# main_backup.net
KiCad netlist of a schematic drawn in Altium Designer
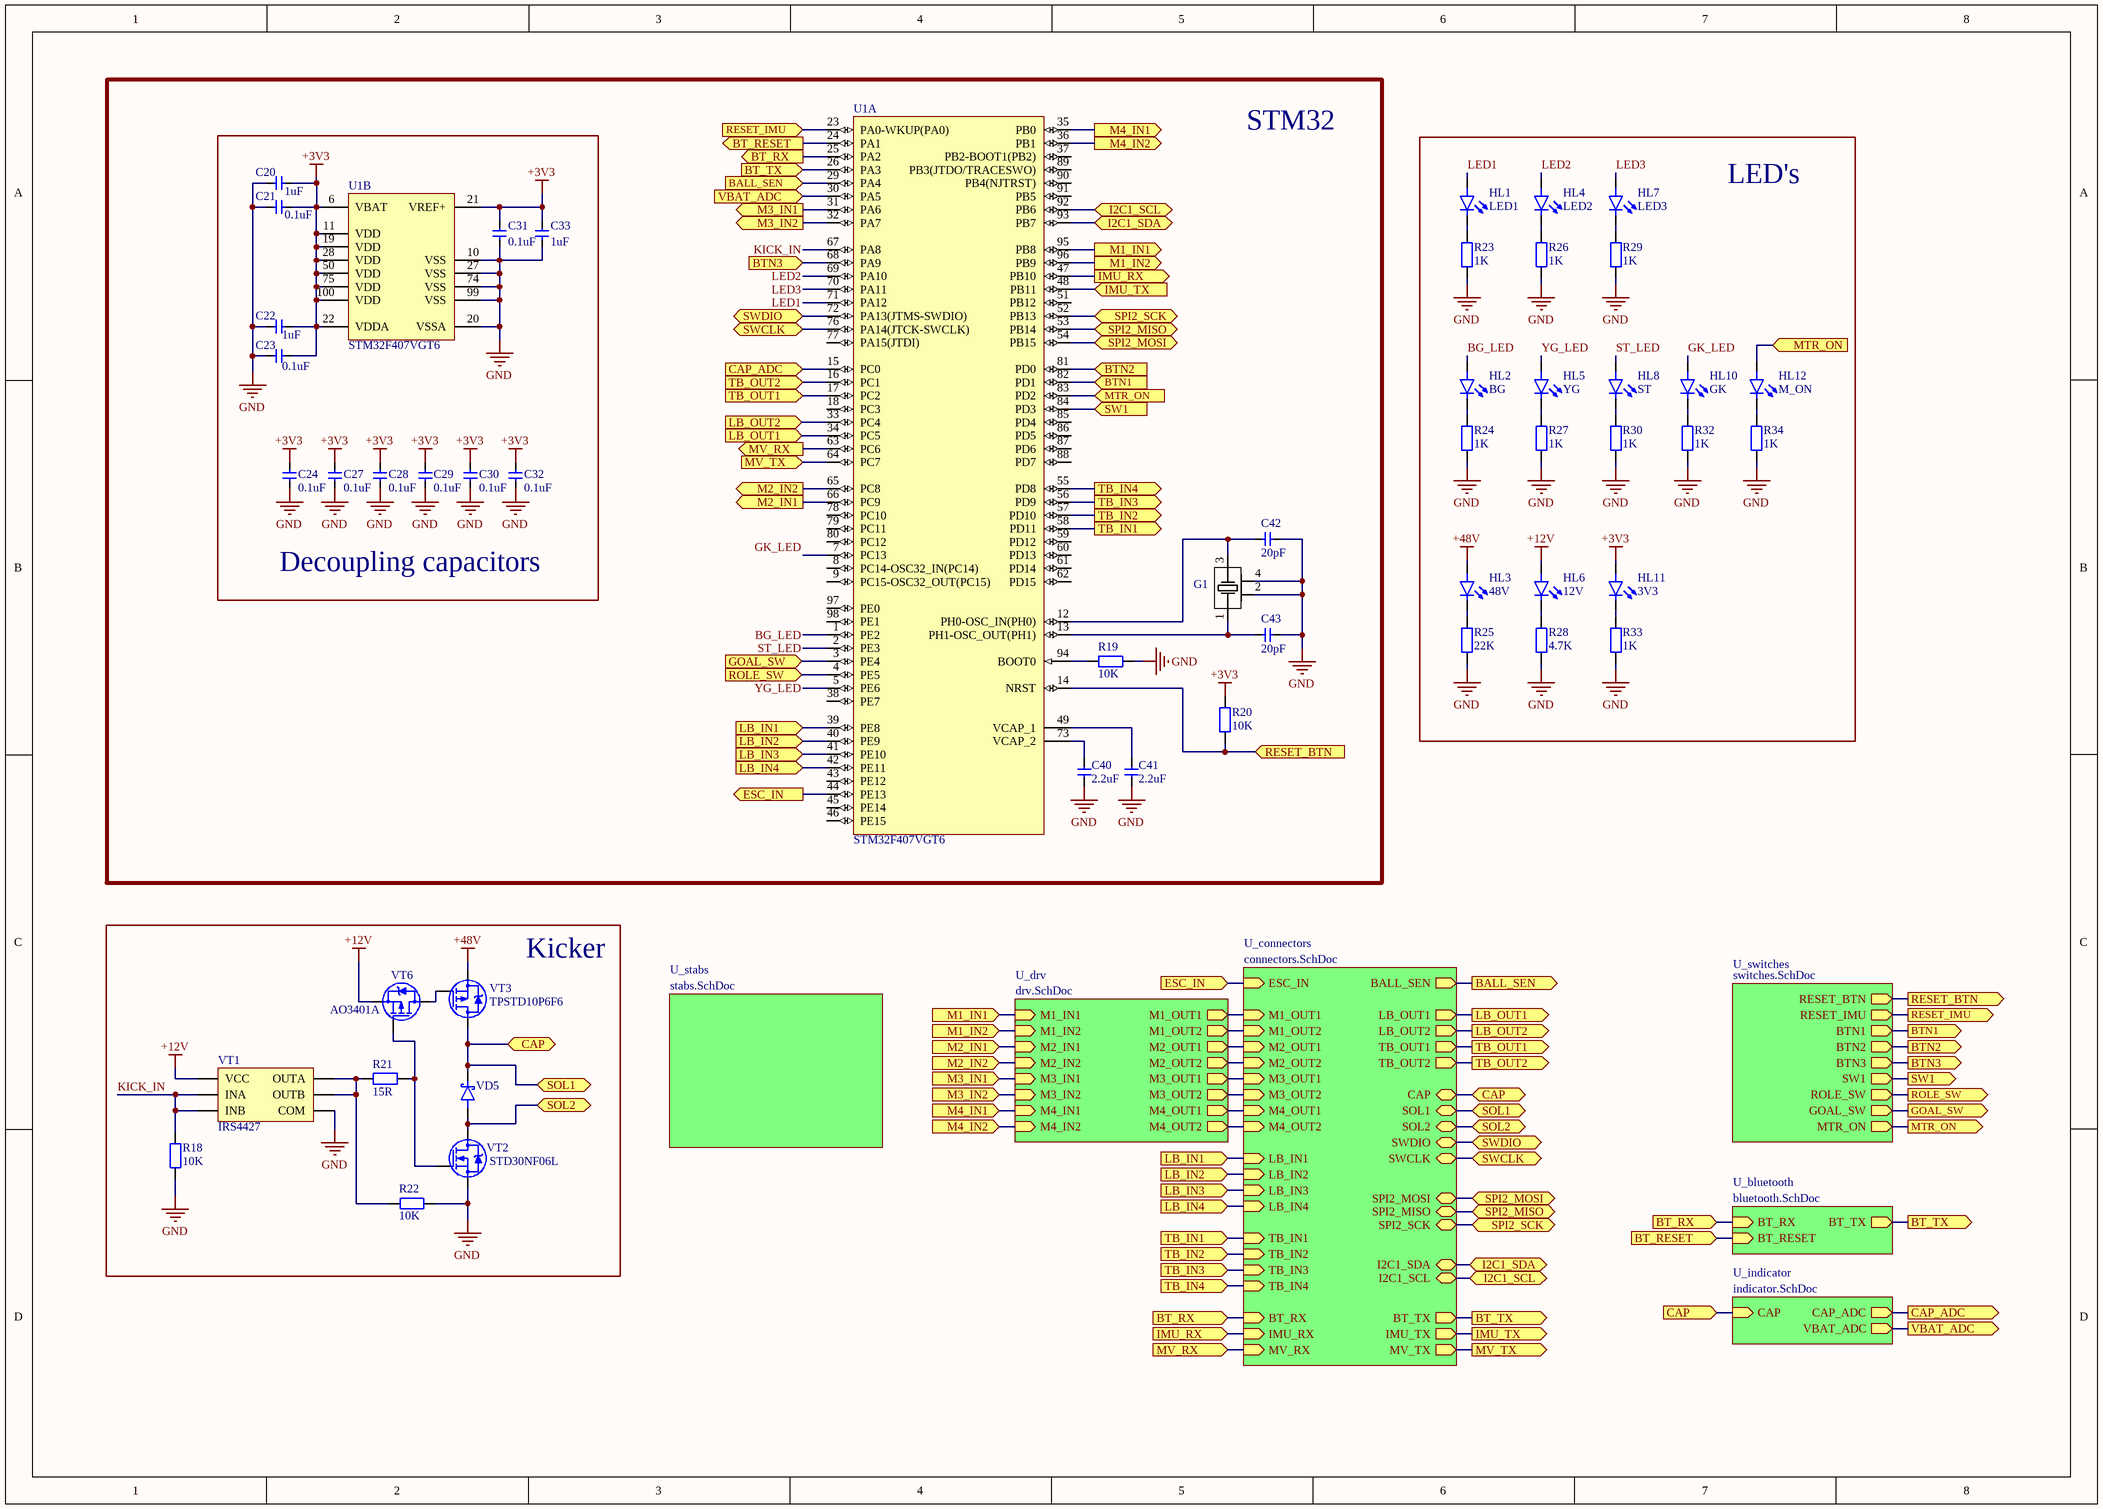
[diagram p0: main_backup.SchDoc]

(export (version "E")
  (design (tool "Eeschema 10.0.6"))
  (components
    (comp (ref "C20")
      (value "1uF")
      (footprint "CAP0805")
      (description "Ceramic SMD Cap")
      (libsource (lib "Asterisk") (part "CAP Ceramic"))
    )
    (comp (ref "C21")
      (value "0.1uF")
      (footprint "CAP0805")
      (description "Ceramic SMD Cap")
      (libsource (lib "Asterisk") (part "CAP Ceramic"))
    )
    (comp (ref "C22")
      (value "1uF")
      (footprint "CAP0805")
      (description "Ceramic SMD Cap")
      (libsource (lib "Asterisk") (part "CAP Ceramic"))
    )
    (comp (ref "C23")
      (value "0.1uF")
      (footprint "CAP0805")
      (description "Ceramic SMD Cap")
      (libsource (lib "Asterisk") (part "CAP Ceramic"))
    )
    (comp (ref "C24")
      (value "0.1uF")
      (footprint "CAP0805")
      (description "Ceramic SMD Cap")
      (libsource (lib "Asterisk") (part "CAP Ceramic"))
    )
    (comp (ref "C27")
      (value "0.1uF")
      (footprint "CAP0805")
      (description "Ceramic SMD Cap")
      (libsource (lib "Asterisk") (part "CAP Ceramic"))
    )
    (comp (ref "C28")
      (value "0.1uF")
      (footprint "CAP0805")
      (description "Ceramic SMD Cap")
      (libsource (lib "Asterisk") (part "CAP Ceramic"))
    )
    (comp (ref "C29")
      (value "0.1uF")
      (footprint "CAP0805")
      (description "Ceramic SMD Cap")
      (libsource (lib "Asterisk") (part "CAP Ceramic"))
    )
    (comp (ref "C30")
      (value "0.1uF")
      (footprint "CAP0805")
      (description "Ceramic SMD Cap")
      (libsource (lib "Asterisk") (part "CAP Ceramic"))
    )
    (comp (ref "C31")
      (value "0.1uF")
      (footprint "CAP0805")
      (description "Ceramic SMD Cap")
      (libsource (lib "Asterisk") (part "CAP Ceramic"))
    )
    (comp (ref "C32")
      (value "0.1uF")
      (footprint "CAP0805")
      (description "Ceramic SMD Cap")
      (libsource (lib "Asterisk") (part "CAP Ceramic"))
    )
    (comp (ref "C33")
      (value "1uF")
      (footprint "CAP0805")
      (description "Ceramic SMD Cap")
      (libsource (lib "Asterisk") (part "CAP Ceramic"))
    )
    (comp (ref "C40")
      (value "2.2uF")
      (footprint "CAP0805")
      (description "Ceramic SMD Cap")
      (libsource (lib "") (part "CAP Ceramic_1"))
    )
    (comp (ref "C41")
      (value "2.2uF")
      (footprint "CAP0805")
      (description "Ceramic SMD Cap")
      (libsource (lib "") (part "CAP Ceramic_1"))
    )
    (comp (ref "C42")
      (value "20pF")
      (footprint "CAP0805")
      (description "Ceramic SMD Cap")
      (libsource (lib "Asterisk") (part "CAP Ceramic"))
    )
    (comp (ref "C43")
      (value "20pF")
      (footprint "CAP0805")
      (description "Ceramic SMD Cap")
      (libsource (lib "Asterisk") (part "CAP Ceramic"))
    )
    (comp (ref "G1")
      (value "8 MHz")
      (footprint "TSX-3225")
      (description "24MHz ±10ppm Crystal 9pF 40 Ohms 4-SMD, No Lead")
      (fields
        (field (name "PART NUMBER") "TSX-3225 24.0000MF15X-AC6")
        (field (name "DIGI-KEY PART NUMBER") "SER4180CT-ND")
      )
      (libsource (lib "SssAccesDatbase") (part "CTX957CT"))
    )
    (comp (ref "HL1")
      (value "LED1")
      (footprint "LED0603_WHITE")
      (description "LED smd")
      (libsource (lib "Asterisk") (part "LED"))
    )
    (comp (ref "HL2")
      (value "BG")
      (footprint "LED0603_WHITE")
      (description "LED smd")
      (libsource (lib "Asterisk") (part "LED"))
    )
    (comp (ref "HL3")
      (value "48V")
      (footprint "LED0603_GREEN")
      (description "LED smd")
      (libsource (lib "Asterisk") (part "LED"))
    )
    (comp (ref "HL4")
      (value "LED2")
      (footprint "LED0603_WHITE")
      (description "LED smd")
      (libsource (lib "Asterisk") (part "LED"))
    )
    (comp (ref "HL5")
      (value "YG")
      (footprint "LED0603_WHITE")
      (description "LED smd")
      (libsource (lib "Asterisk") (part "LED"))
    )
    (comp (ref "HL6")
      (value "12V")
      (footprint "LED0603_GREEN")
      (description "LED smd")
      (libsource (lib "Asterisk") (part "LED"))
    )
    (comp (ref "HL7")
      (value "LED3")
      (footprint "LED0603_WHITE")
      (description "LED smd")
      (libsource (lib "Asterisk") (part "LED"))
    )
    (comp (ref "HL8")
      (value "ST")
      (footprint "LED0603_WHITE")
      (description "LED smd")
      (libsource (lib "Asterisk") (part "LED"))
    )
    (comp (ref "HL10")
      (value "GK")
      (footprint "LED0603_WHITE")
      (description "LED smd")
      (libsource (lib "Asterisk") (part "LED"))
    )
    (comp (ref "HL11")
      (value "3V3")
      (footprint "LED0603_GREEN")
      (description "LED smd")
      (libsource (lib "Asterisk") (part "LED"))
    )
    (comp (ref "HL12")
      (value "M_ON")
      (footprint "LED0603_RED")
      (description "LED smd")
      (libsource (lib "Asterisk") (part "LED"))
    )
    (comp (ref "R18")
      (value "10K")
      (footprint "RES0805")
      (description "RES smd")
      (libsource (lib "Asterisk") (part "RES"))
    )
    (comp (ref "R19")
      (value "10K")
      (footprint "RES0805")
      (description "RES smd")
      (libsource (lib "Asterisk") (part "RES"))
    )
    (comp (ref "R20")
      (value "10K")
      (footprint "RES0805")
      (description "RES smd")
      (libsource (lib "Asterisk") (part "RES"))
    )
    (comp (ref "R21")
      (value "15R")
      (footprint "RES1206")
      (description "RES smd")
      (libsource (lib "Asterisk") (part "RES"))
    )
    (comp (ref "R22")
      (value "10K")
      (footprint "RES0805")
      (description "RES smd")
      (libsource (lib "Asterisk") (part "RES"))
    )
    (comp (ref "R23")
      (value "1K")
      (footprint "RES0805")
      (description "RES smd")
      (libsource (lib "Asterisk") (part "RES"))
    )
    (comp (ref "R24")
      (value "1K")
      (footprint "RES0805")
      (description "RES smd")
      (libsource (lib "Asterisk") (part "RES"))
    )
    (comp (ref "R25")
      (value "22K")
      (footprint "RES0805")
      (description "RES smd")
      (libsource (lib "Asterisk") (part "RES"))
    )
    (comp (ref "R26")
      (value "1K")
      (footprint "RES0805")
      (description "RES smd")
      (libsource (lib "Asterisk") (part "RES"))
    )
    (comp (ref "R27")
      (value "1K")
      (footprint "RES0805")
      (description "RES smd")
      (libsource (lib "Asterisk") (part "RES"))
    )
    (comp (ref "R28")
      (value "4.7K")
      (footprint "RES0805")
      (description "RES smd")
      (libsource (lib "Asterisk") (part "RES"))
    )
    (comp (ref "R29")
      (value "1K")
      (footprint "RES0805")
      (description "RES smd")
      (libsource (lib "Asterisk") (part "RES"))
    )
    (comp (ref "R30")
      (value "1K")
      (footprint "RES0805")
      (description "RES smd")
      (libsource (lib "Asterisk") (part "RES"))
    )
    (comp (ref "R32")
      (value "1K")
      (footprint "RES0805")
      (description "RES smd")
      (libsource (lib "Asterisk") (part "RES"))
    )
    (comp (ref "R33")
      (value "1K")
      (footprint "RES0805")
      (description "RES smd")
      (libsource (lib "Asterisk") (part "RES"))
    )
    (comp (ref "R34")
      (value "1K")
      (footprint "RES0805")
      (description "RES smd")
      (libsource (lib "Asterisk") (part "RES"))
    )
    (comp (ref "U1")
      (value "STM32F407VGT6")
      (footprint "LQFP100")
      (fields (field (name "MANUFACTURER") "STMicroelectronics"))
      (libsource (lib "Asterisk") (part "STM32F407VGT6"))
    )
    (comp (ref "VD5")
      (value "Diode Schottky")
      (footprint "DO-214AC (SMA)")
      (libsource (lib "Asterisk") (part "Diode Schottky"))
    )
    (comp (ref "VT1")
      (value "IRS4427")
      (footprint "SOIC-8")
      (description "Mosfet driver")
      (libsource (lib "Asterisk") (part "IRS4427"))
    )
    (comp (ref "VT2")
      (value "STD30NF06L")
      (footprint "DPAK")
      (description "N-MOSFET\r\nUds = 60 V\r\nIds = 30 A\r\nRds = 0.023 Ohm\r\nP = 55 W")
      (libsource (lib "Asterisk") (part "STD30NF06L"))
    )
    (comp (ref "VT3")
      (value "TPSTD10P6F6")
      (footprint "DPAK")
      (description "P-MOSFET\r\nUds = 60 V\r\nIds = 13 A\r\nRds = 0.100 Ohm\r\nP = 60 W")
      (libsource (lib "Asterisk") (part "TPSTD10P6F6"))
    )
    (comp (ref "VT6")
      (value "AO3401A")
      (footprint "SOT-23-3")
      (description "P-MOSFET\r\nUds = 30 V\r\nIds = 4.2 A\r\nRds = 0.050 Ohm\r\nP = 1.4 W")
      (libsource (lib "Asterisk") (part "AO3401A"))
    )
  )
  (nets
    (net (code "1") (name "+3V3") (class "Default")
      (node (ref "C20") (pin "1") (pinfunction "1_1") (pintype "passive"))
      (node (ref "C21") (pin "1") (pinfunction "1_1") (pintype "passive"))
      (node (ref "C22") (pin "1") (pinfunction "1_1") (pintype "passive"))
      (node (ref "C23") (pin "1") (pinfunction "1_1") (pintype "passive"))
      (node (ref "C24") (pin "1") (pinfunction "1_1") (pintype "passive"))
      (node (ref "C27") (pin "1") (pinfunction "1_1") (pintype "passive"))
      (node (ref "C28") (pin "1") (pinfunction "1_1") (pintype "passive"))
      (node (ref "C29") (pin "1") (pinfunction "1_1") (pintype "passive"))
      (node (ref "C30") (pin "1") (pinfunction "1_1") (pintype "passive"))
      (node (ref "C31") (pin "2") (pinfunction "2_2") (pintype "passive"))
      (node (ref "C32") (pin "1") (pinfunction "1_1") (pintype "passive"))
      (node (ref "C33") (pin "2") (pinfunction "2_2") (pintype "passive"))
      (node (ref "HL11") (pin "2") (pinfunction "A_2") (pintype "passive"))
      (node (ref "R20") (pin "1") (pinfunction "1_1") (pintype "passive"))
      (node (ref "U1") (pin "100") (pinfunction "VDD_100") (pintype "power_in"))
      (node (ref "U1") (pin "11") (pinfunction "VDD_11") (pintype "power_in"))
      (node (ref "U1") (pin "19") (pinfunction "VDD_19") (pintype "power_in"))
      (node (ref "U1") (pin "21") (pinfunction "VREF+_21") (pintype "power_in"))
      (node (ref "U1") (pin "22") (pinfunction "VDDA_22") (pintype "power_in"))
      (node (ref "U1") (pin "28") (pinfunction "VDD_28") (pintype "power_in"))
      (node (ref "U1") (pin "50") (pinfunction "VDD_50") (pintype "power_in"))
      (node (ref "U1") (pin "6") (pinfunction "VBAT_6") (pintype "power_in"))
      (node (ref "U1") (pin "75") (pinfunction "VDD_75") (pintype "power_in"))
    )
    (net (code "2") (name "+12V") (class "Default")
      (node (ref "HL6") (pin "2") (pinfunction "A_2") (pintype "passive"))
      (node (ref "VT1") (pin "6") (pinfunction "VCC_6") (pintype "passive"))
      (node (ref "VT6") (pin "S") (pinfunction "S_S") (pintype "passive"))
    )
    (net (code "3") (name "+48V") (class "Default")
      (node (ref "HL3") (pin "2") (pinfunction "A_2") (pintype "passive"))
      (node (ref "VT3") (pin "S") (pinfunction "S_S") (pintype "passive"))
    )
    (net (code "4") (name "/BALL_SEN") (class "Default")
      (node (ref "U1") (pin "29") (pinfunction "PA4_29") (pintype "bidirectional"))
    )
    (net (code "5") (name "/BG_LED") (class "Default")
      (node (ref "HL2") (pin "2") (pinfunction "A_2") (pintype "passive"))
      (node (ref "U1") (pin "1") (pinfunction "PE2_1") (pintype "bidirectional"))
    )
    (net (code "6") (name "/BTN1") (class "Default")
      (node (ref "U1") (pin "82") (pinfunction "PD1_82") (pintype "bidirectional"))
    )
    (net (code "7") (name "/BTN2") (class "Default")
      (node (ref "U1") (pin "81") (pinfunction "PD0_81") (pintype "bidirectional"))
    )
    (net (code "8") (name "/BTN3") (class "Default")
      (node (ref "U1") (pin "68") (pinfunction "PA9_68") (pintype "bidirectional"))
    )
    (net (code "9") (name "/BT_RESET") (class "Default")
      (node (ref "U1") (pin "24") (pinfunction "PA1_24") (pintype "bidirectional"))
    )
    (net (code "10") (name "/BT_RX") (class "Default")
      (node (ref "U1") (pin "25") (pinfunction "PA2_25") (pintype "bidirectional"))
    )
    (net (code "11") (name "/BT_TX") (class "Default")
      (node (ref "U1") (pin "26") (pinfunction "PA3_26") (pintype "bidirectional"))
    )
    (net (code "12") (name "/CAP") (class "Default")
      (node (ref "VD5") (pin "K") (pinfunction "K_K") (pintype "passive"))
      (node (ref "VT3") (pin "D") (pinfunction "D_D") (pintype "passive"))
    )
    (net (code "13") (name "/CAP_ADC") (class "Default")
      (node (ref "U1") (pin "15") (pinfunction "PC0_15") (pintype "bidirectional"))
    )
    (net (code "14") (name "/ESC_IN") (class "Default")
      (node (ref "U1") (pin "44") (pinfunction "PE13_44") (pintype "bidirectional"))
    )
    (net (code "15") (name "/GK_LED") (class "Default")
      (node (ref "HL10") (pin "2") (pinfunction "A_2") (pintype "passive"))
      (node (ref "U1") (pin "7") (pinfunction "PC13_7") (pintype "bidirectional"))
    )
    (net (code "16") (name "/GOAL_SW") (class "Default")
      (node (ref "U1") (pin "3") (pinfunction "PE4_3") (pintype "bidirectional"))
    )
    (net (code "17") (name "/I2C1_SCL") (class "Default")
      (node (ref "U1") (pin "92") (pinfunction "PB6_92") (pintype "bidirectional"))
    )
    (net (code "18") (name "/I2C1_SDA") (class "Default")
      (node (ref "U1") (pin "93") (pinfunction "PB7_93") (pintype "bidirectional"))
    )
    (net (code "19") (name "/IMU_RX") (class "Default")
      (node (ref "U1") (pin "47") (pinfunction "PB10_47") (pintype "bidirectional"))
    )
    (net (code "20") (name "/IMU_TX") (class "Default")
      (node (ref "U1") (pin "48") (pinfunction "PB11_48") (pintype "bidirectional"))
    )
    (net (code "21") (name "/KICK_IN") (class "Default")
      (node (ref "R18") (pin "2") (pinfunction "2_2") (pintype "passive"))
      (node (ref "U1") (pin "67") (pinfunction "PA8_67") (pintype "bidirectional"))
      (node (ref "VT1") (pin "2") (pinfunction "INA_2") (pintype "passive"))
      (node (ref "VT1") (pin "4") (pinfunction "INB_4") (pintype "passive"))
    )
    (net (code "22") (name "/LB_IN1") (class "Default")
      (node (ref "U1") (pin "39") (pinfunction "PE8_39") (pintype "bidirectional"))
    )
    (net (code "23") (name "/LB_IN2") (class "Default")
      (node (ref "U1") (pin "40") (pinfunction "PE9_40") (pintype "bidirectional"))
    )
    (net (code "24") (name "/LB_IN3") (class "Default")
      (node (ref "U1") (pin "41") (pinfunction "PE10_41") (pintype "bidirectional"))
    )
    (net (code "25") (name "/LB_IN4") (class "Default")
      (node (ref "U1") (pin "42") (pinfunction "PE11_42") (pintype "bidirectional"))
    )
    (net (code "26") (name "/LB_OUT1") (class "Default")
      (node (ref "U1") (pin "34") (pinfunction "PC5_34") (pintype "bidirectional"))
    )
    (net (code "27") (name "/LB_OUT2") (class "Default")
      (node (ref "U1") (pin "33") (pinfunction "PC4_33") (pintype "bidirectional"))
    )
    (net (code "28") (name "/LED1") (class "Default")
      (node (ref "HL1") (pin "2") (pinfunction "A_2") (pintype "passive"))
      (node (ref "U1") (pin "71") (pinfunction "PA12_71") (pintype "bidirectional"))
    )
    (net (code "29") (name "/LED2") (class "Default")
      (node (ref "HL4") (pin "2") (pinfunction "A_2") (pintype "passive"))
      (node (ref "U1") (pin "69") (pinfunction "PA10_69") (pintype "bidirectional"))
    )
    (net (code "30") (name "/LED3") (class "Default")
      (node (ref "HL7") (pin "2") (pinfunction "A_2") (pintype "passive"))
      (node (ref "U1") (pin "70") (pinfunction "PA11_70") (pintype "bidirectional"))
    )
    (net (code "31") (name "/M1_IN1") (class "Default")
      (node (ref "U1") (pin "95") (pinfunction "PB8_95") (pintype "bidirectional"))
    )
    (net (code "32") (name "/M1_IN2") (class "Default")
      (node (ref "U1") (pin "96") (pinfunction "PB9_96") (pintype "bidirectional"))
    )
    (net (code "35") (name "/M2_IN1") (class "Default")
      (node (ref "U1") (pin "66") (pinfunction "PC9_66") (pintype "bidirectional"))
    )
    (net (code "36") (name "/M2_IN2") (class "Default")
      (node (ref "U1") (pin "65") (pinfunction "PC8_65") (pintype "bidirectional"))
    )
    (net (code "39") (name "/M3_IN1") (class "Default")
      (node (ref "U1") (pin "31") (pinfunction "PA6_31") (pintype "bidirectional"))
    )
    (net (code "40") (name "/M3_IN2") (class "Default")
      (node (ref "U1") (pin "32") (pinfunction "PA7_32") (pintype "bidirectional"))
    )
    (net (code "43") (name "/M4_IN1") (class "Default")
      (node (ref "U1") (pin "35") (pinfunction "PB0_35") (pintype "bidirectional"))
    )
    (net (code "44") (name "/M4_IN2") (class "Default")
      (node (ref "U1") (pin "36") (pinfunction "PB1_36") (pintype "bidirectional"))
    )
    (net (code "47") (name "/MTR_ON") (class "Default")
      (node (ref "HL12") (pin "2") (pinfunction "A_2") (pintype "passive"))
      (node (ref "U1") (pin "83") (pinfunction "PD2_83") (pintype "bidirectional"))
    )
    (net (code "48") (name "/MV_RX") (class "Default")
      (node (ref "U1") (pin "63") (pinfunction "PC6_63") (pintype "bidirectional"))
    )
    (net (code "49") (name "/MV_TX") (class "Default")
      (node (ref "U1") (pin "64") (pinfunction "PC7_64") (pintype "bidirectional"))
    )
    (net (code "50") (name "/RESET_BTN") (class "Default")
      (node (ref "R20") (pin "2") (pinfunction "2_2") (pintype "passive"))
      (node (ref "U1") (pin "14") (pinfunction "NRST_14") (pintype "bidirectional"))
    )
    (net (code "51") (name "/RESET_IMU") (class "Default")
      (node (ref "U1") (pin "23") (pinfunction "PA0-WKUP(PA0)_23") (pintype "bidirectional"))
    )
    (net (code "52") (name "/ROLE_SW") (class "Default")
      (node (ref "U1") (pin "4") (pinfunction "PE5_4") (pintype "bidirectional"))
    )
    (net (code "53") (name "/SOL2") (class "Default")
      (node (ref "VD5") (pin "A") (pinfunction "A_A") (pintype "passive"))
      (node (ref "VT2") (pin "D") (pinfunction "D_D") (pintype "passive"))
    )
    (net (code "54") (name "/SPI2_MISO") (class "Default")
      (node (ref "U1") (pin "53") (pinfunction "PB14_53") (pintype "bidirectional"))
    )
    (net (code "55") (name "/SPI2_MOSI") (class "Default")
      (node (ref "U1") (pin "54") (pinfunction "PB15_54") (pintype "bidirectional"))
    )
    (net (code "56") (name "/SPI2_SCK") (class "Default")
      (node (ref "U1") (pin "52") (pinfunction "PB13_52") (pintype "bidirectional"))
    )
    (net (code "57") (name "/ST_LED") (class "Default")
      (node (ref "HL8") (pin "2") (pinfunction "A_2") (pintype "passive"))
      (node (ref "U1") (pin "2") (pinfunction "PE3_2") (pintype "bidirectional"))
    )
    (net (code "58") (name "/SW1") (class "Default")
      (node (ref "U1") (pin "84") (pinfunction "PD3_84") (pintype "bidirectional"))
    )
    (net (code "59") (name "/SWCLK") (class "Default")
      (node (ref "U1") (pin "76") (pinfunction "PA14(JTCK-SWCLK)_76") (pintype "bidirectional"))
    )
    (net (code "60") (name "/SWDIO") (class "Default")
      (node (ref "U1") (pin "72") (pinfunction "PA13(JTMS-SWDIO)_72") (pintype "bidirectional"))
    )
    (net (code "61") (name "/TB_IN1") (class "Default")
      (node (ref "U1") (pin "58") (pinfunction "PD11_58") (pintype "bidirectional"))
    )
    (net (code "62") (name "/TB_IN2") (class "Default")
      (node (ref "U1") (pin "57") (pinfunction "PD10_57") (pintype "bidirectional"))
    )
    (net (code "63") (name "/TB_IN3") (class "Default")
      (node (ref "U1") (pin "56") (pinfunction "PD9_56") (pintype "bidirectional"))
    )
    (net (code "64") (name "/TB_IN4") (class "Default")
      (node (ref "U1") (pin "55") (pinfunction "PD8_55") (pintype "bidirectional"))
    )
    (net (code "65") (name "/TB_OUT1") (class "Default")
      (node (ref "U1") (pin "17") (pinfunction "PC2_17") (pintype "bidirectional"))
    )
    (net (code "66") (name "/TB_OUT2") (class "Default")
      (node (ref "U1") (pin "16") (pinfunction "PC1_16") (pintype "bidirectional"))
    )
    (net (code "67") (name "/VBAT_ADC") (class "Default")
      (node (ref "U1") (pin "30") (pinfunction "PA5_30") (pintype "bidirectional"))
    )
    (net (code "68") (name "/YG_LED") (class "Default")
      (node (ref "HL5") (pin "2") (pinfunction "A_2") (pintype "passive"))
      (node (ref "U1") (pin "5") (pinfunction "PE6_5") (pintype "bidirectional"))
    )
    (net (code "69") (name "GND") (class "Default")
      (node (ref "C20") (pin "2") (pinfunction "2_2") (pintype "passive"))
      (node (ref "C21") (pin "2") (pinfunction "2_2") (pintype "passive"))
      (node (ref "C22") (pin "2") (pinfunction "2_2") (pintype "passive"))
      (node (ref "C23") (pin "2") (pinfunction "2_2") (pintype "passive"))
      (node (ref "C24") (pin "2") (pinfunction "2_2") (pintype "passive"))
      (node (ref "C27") (pin "2") (pinfunction "2_2") (pintype "passive"))
      (node (ref "C28") (pin "2") (pinfunction "2_2") (pintype "passive"))
      (node (ref "C29") (pin "2") (pinfunction "2_2") (pintype "passive"))
      (node (ref "C30") (pin "2") (pinfunction "2_2") (pintype "passive"))
      (node (ref "C31") (pin "1") (pinfunction "1_1") (pintype "passive"))
      (node (ref "C32") (pin "2") (pinfunction "2_2") (pintype "passive"))
      (node (ref "C33") (pin "1") (pinfunction "1_1") (pintype "passive"))
      (node (ref "C40") (pin "1") (pinfunction "1_1") (pintype "passive"))
      (node (ref "C41") (pin "1") (pinfunction "1_1") (pintype "passive"))
      (node (ref "C42") (pin "2") (pinfunction "2_2") (pintype "passive"))
      (node (ref "C43") (pin "2") (pinfunction "2_2") (pintype "passive"))
      (node (ref "G1") (pin "2") (pinfunction "2_2") (pintype "passive"))
      (node (ref "G1") (pin "4") (pinfunction "4_4") (pintype "passive"))
      (node (ref "R18") (pin "1") (pinfunction "1_1") (pintype "passive"))
      (node (ref "R19") (pin "1") (pinfunction "1_1") (pintype "passive"))
      (node (ref "R22") (pin "2") (pinfunction "2_2") (pintype "passive"))
      (node (ref "R23") (pin "1") (pinfunction "1_1") (pintype "passive"))
      (node (ref "R24") (pin "1") (pinfunction "1_1") (pintype "passive"))
      (node (ref "R25") (pin "1") (pinfunction "1_1") (pintype "passive"))
      (node (ref "R26") (pin "1") (pinfunction "1_1") (pintype "passive"))
      (node (ref "R27") (pin "1") (pinfunction "1_1") (pintype "passive"))
      (node (ref "R28") (pin "1") (pinfunction "1_1") (pintype "passive"))
      (node (ref "R29") (pin "1") (pinfunction "1_1") (pintype "passive"))
      (node (ref "R30") (pin "1") (pinfunction "1_1") (pintype "passive"))
      (node (ref "R32") (pin "1") (pinfunction "1_1") (pintype "passive"))
      (node (ref "R33") (pin "1") (pinfunction "1_1") (pintype "passive"))
      (node (ref "R34") (pin "1") (pinfunction "1_1") (pintype "passive"))
      (node (ref "U1") (pin "10") (pinfunction "VSS_10") (pintype "power_in"))
      (node (ref "U1") (pin "20") (pinfunction "VSSA_20") (pintype "power_in"))
      (node (ref "U1") (pin "27") (pinfunction "VSS_27") (pintype "power_in"))
      (node (ref "U1") (pin "74") (pinfunction "VSS_74") (pintype "power_in"))
      (node (ref "U1") (pin "99") (pinfunction "VSS_99") (pintype "power_in"))
      (node (ref "VT1") (pin "3") (pinfunction "COM_3") (pintype "passive"))
      (node (ref "VT2") (pin "S") (pinfunction "S_S") (pintype "passive"))
    )
    (net (code "70") (name "Net-(HL1-K)") (class "Default")
      (node (ref "HL1") (pin "1") (pinfunction "K_1") (pintype "passive"))
      (node (ref "R23") (pin "2") (pinfunction "2_2") (pintype "passive"))
    )
    (net (code "71") (name "Net-(HL2-K)") (class "Default")
      (node (ref "HL2") (pin "1") (pinfunction "K_1") (pintype "passive"))
      (node (ref "R24") (pin "2") (pinfunction "2_2") (pintype "passive"))
    )
    (net (code "72") (name "Net-(HL3-K)") (class "Default")
      (node (ref "HL3") (pin "1") (pinfunction "K_1") (pintype "passive"))
      (node (ref "R25") (pin "2") (pinfunction "2_2") (pintype "passive"))
    )
    (net (code "73") (name "Net-(HL4-K)") (class "Default")
      (node (ref "HL4") (pin "1") (pinfunction "K_1") (pintype "passive"))
      (node (ref "R26") (pin "2") (pinfunction "2_2") (pintype "passive"))
    )
    (net (code "74") (name "Net-(HL5-K)") (class "Default")
      (node (ref "HL5") (pin "1") (pinfunction "K_1") (pintype "passive"))
      (node (ref "R27") (pin "2") (pinfunction "2_2") (pintype "passive"))
    )
    (net (code "75") (name "Net-(HL6-K)") (class "Default")
      (node (ref "HL6") (pin "1") (pinfunction "K_1") (pintype "passive"))
      (node (ref "R28") (pin "2") (pinfunction "2_2") (pintype "passive"))
    )
    (net (code "76") (name "Net-(HL7-K)") (class "Default")
      (node (ref "HL7") (pin "1") (pinfunction "K_1") (pintype "passive"))
      (node (ref "R29") (pin "2") (pinfunction "2_2") (pintype "passive"))
    )
    (net (code "77") (name "Net-(HL8-K)") (class "Default")
      (node (ref "HL8") (pin "1") (pinfunction "K_1") (pintype "passive"))
      (node (ref "R30") (pin "2") (pinfunction "2_2") (pintype "passive"))
    )
    (net (code "78") (name "Net-(HL10-K)") (class "Default")
      (node (ref "HL10") (pin "1") (pinfunction "K_1") (pintype "passive"))
      (node (ref "R32") (pin "2") (pinfunction "2_2") (pintype "passive"))
    )
    (net (code "79") (name "Net-(HL11-K)") (class "Default")
      (node (ref "HL11") (pin "1") (pinfunction "K_1") (pintype "passive"))
      (node (ref "R33") (pin "2") (pinfunction "2_2") (pintype "passive"))
    )
    (net (code "80") (name "Net-(HL12-K)") (class "Default")
      (node (ref "HL12") (pin "1") (pinfunction "K_1") (pintype "passive"))
      (node (ref "R34") (pin "2") (pinfunction "2_2") (pintype "passive"))
    )
    (net (code "81") (name "Net-(R21-Pad2)") (class "Default")
      (node (ref "R21") (pin "2") (pinfunction "2_2") (pintype "passive"))
      (node (ref "VT2") (pin "G") (pinfunction "G_G") (pintype "passive"))
      (node (ref "VT6") (pin "G") (pinfunction "G_G") (pintype "passive"))
    )
    (net (code "82") (name "Net-(U1A-BOOT0)") (class "Default")
      (node (ref "R19") (pin "2") (pinfunction "2_2") (pintype "passive"))
      (node (ref "U1") (pin "94") (pinfunction "BOOT0_94") (pintype "input"))
    )
    (net (code "83") (name "Net-(U1A-PH0-OSC_IN(PH0))") (class "Default")
      (node (ref "C42") (pin "1") (pinfunction "1_1") (pintype "passive"))
      (node (ref "G1") (pin "3") (pinfunction "3_3") (pintype "passive"))
      (node (ref "U1") (pin "12") (pinfunction "PH0-OSC_IN(PH0)_12") (pintype "bidirectional"))
    )
    (net (code "84") (name "Net-(U1A-PH1-OSC_OUT(PH1))") (class "Default")
      (node (ref "C43") (pin "1") (pinfunction "1_1") (pintype "passive"))
      (node (ref "G1") (pin "1") (pinfunction "1_1") (pintype "passive"))
      (node (ref "U1") (pin "13") (pinfunction "PH1-OSC_OUT(PH1)_13") (pintype "bidirectional"))
    )
    (net (code "85") (name "Net-(U1A-VCAP_1)") (class "Default")
      (node (ref "C41") (pin "2") (pinfunction "2_2") (pintype "passive"))
      (node (ref "U1") (pin "49") (pinfunction "VCAP_1_49") (pintype "power_in"))
    )
    (net (code "86") (name "Net-(U1A-VCAP_2)") (class "Default")
      (node (ref "C40") (pin "2") (pinfunction "2_2") (pintype "passive"))
      (node (ref "U1") (pin "73") (pinfunction "VCAP_2_73") (pintype "power_in"))
    )
    (net (code "87") (name "Net-(VT1-OUTA)") (class "Default")
      (node (ref "R21") (pin "1") (pinfunction "1_1") (pintype "passive"))
      (node (ref "R22") (pin "1") (pinfunction "1_1") (pintype "passive"))
      (node (ref "VT1") (pin "5") (pinfunction "OUTB_5") (pintype "passive"))
      (node (ref "VT1") (pin "7") (pinfunction "OUTA_7") (pintype "passive"))
    )
    (net (code "88") (name "Net-(VT3-PadG)") (class "Default")
      (node (ref "VT3") (pin "G") (pinfunction "G_G") (pintype "passive"))
      (node (ref "VT6") (pin "D") (pinfunction "D_D") (pintype "passive"))
    )
    (net (code "89") (name "unconnected-(U1A-PA15(JTDI)-Pad77)") (class "Default")
      (node (ref "U1") (pin "77") (pinfunction "PA15(JTDI)_77") (pintype "bidirectional"))
    )
    (net (code "90") (name "unconnected-(U1A-PB2-BOOT1(PB2)-Pad37)") (class "Default")
      (node (ref "U1") (pin "37") (pinfunction "PB2-BOOT1(PB2)_37") (pintype "bidirectional"))
    )
    (net (code "91") (name "unconnected-(U1A-PB3(JTDO{slash}TRACESWO)-Pad89)") (class "Default")
      (node (ref "U1") (pin "89") (pinfunction "PB3(JTDO/TRACESWO)_89") (pintype "bidirectional"))
    )
    (net (code "92") (name "unconnected-(U1A-PB4(NJTRST)-Pad90)") (class "Default")
      (node (ref "U1") (pin "90") (pinfunction "PB4(NJTRST)_90") (pintype "bidirectional"))
    )
    (net (code "93") (name "unconnected-(U1A-PB5-Pad91)") (class "Default")
      (node (ref "U1") (pin "91") (pinfunction "PB5_91") (pintype "bidirectional"))
    )
    (net (code "94") (name "unconnected-(U1A-PB12-Pad51)") (class "Default")
      (node (ref "U1") (pin "51") (pinfunction "PB12_51") (pintype "bidirectional"))
    )
    (net (code "95") (name "unconnected-(U1A-PC3-Pad18)") (class "Default")
      (node (ref "U1") (pin "18") (pinfunction "PC3_18") (pintype "bidirectional"))
    )
    (net (code "96") (name "unconnected-(U1A-PC10-Pad78)") (class "Default")
      (node (ref "U1") (pin "78") (pinfunction "PC10_78") (pintype "bidirectional"))
    )
    (net (code "97") (name "unconnected-(U1A-PC11-Pad79)") (class "Default")
      (node (ref "U1") (pin "79") (pinfunction "PC11_79") (pintype "bidirectional"))
    )
    (net (code "98") (name "unconnected-(U1A-PC12-Pad80)") (class "Default")
      (node (ref "U1") (pin "80") (pinfunction "PC12_80") (pintype "bidirectional"))
    )
    (net (code "99") (name "unconnected-(U1A-PC14-OSC32_IN(PC14)-Pad8)") (class "Default")
      (node (ref "U1") (pin "8") (pinfunction "PC14-OSC32_IN(PC14)_8") (pintype "bidirectional"))
    )
    (net (code "100") (name "unconnected-(U1A-PC15-OSC32_OUT(PC15)-Pad9)") (class "Default")
      (node (ref "U1") (pin "9") (pinfunction "PC15-OSC32_OUT(PC15)_9") (pintype "bidirectional"))
    )
    (net (code "101") (name "unconnected-(U1A-PD4-Pad85)") (class "Default")
      (node (ref "U1") (pin "85") (pinfunction "PD4_85") (pintype "bidirectional"))
    )
    (net (code "102") (name "unconnected-(U1A-PD5-Pad86)") (class "Default")
      (node (ref "U1") (pin "86") (pinfunction "PD5_86") (pintype "bidirectional"))
    )
    (net (code "103") (name "unconnected-(U1A-PD6-Pad87)") (class "Default")
      (node (ref "U1") (pin "87") (pinfunction "PD6_87") (pintype "bidirectional"))
    )
    (net (code "104") (name "unconnected-(U1A-PD7-Pad88)") (class "Default")
      (node (ref "U1") (pin "88") (pinfunction "PD7_88") (pintype "bidirectional"))
    )
    (net (code "105") (name "unconnected-(U1A-PD12-Pad59)") (class "Default")
      (node (ref "U1") (pin "59") (pinfunction "PD12_59") (pintype "bidirectional"))
    )
    (net (code "106") (name "unconnected-(U1A-PD13-Pad60)") (class "Default")
      (node (ref "U1") (pin "60") (pinfunction "PD13_60") (pintype "bidirectional"))
    )
    (net (code "107") (name "unconnected-(U1A-PD14-Pad61)") (class "Default")
      (node (ref "U1") (pin "61") (pinfunction "PD14_61") (pintype "bidirectional"))
    )
    (net (code "108") (name "unconnected-(U1A-PD15-Pad62)") (class "Default")
      (node (ref "U1") (pin "62") (pinfunction "PD15_62") (pintype "bidirectional"))
    )
    (net (code "109") (name "unconnected-(U1A-PE0-Pad97)") (class "Default")
      (node (ref "U1") (pin "97") (pinfunction "PE0_97") (pintype "bidirectional"))
    )
    (net (code "110") (name "unconnected-(U1A-PE1-Pad98)") (class "Default")
      (node (ref "U1") (pin "98") (pinfunction "PE1_98") (pintype "bidirectional"))
    )
    (net (code "111") (name "unconnected-(U1A-PE7-Pad38)") (class "Default")
      (node (ref "U1") (pin "38") (pinfunction "PE7_38") (pintype "bidirectional"))
    )
    (net (code "112") (name "unconnected-(U1A-PE12-Pad43)") (class "Default")
      (node (ref "U1") (pin "43") (pinfunction "PE12_43") (pintype "bidirectional"))
    )
    (net (code "113") (name "unconnected-(U1A-PE14-Pad45)") (class "Default")
      (node (ref "U1") (pin "45") (pinfunction "PE14_45") (pintype "bidirectional"))
    )
    (net (code "114") (name "unconnected-(U1A-PE15-Pad46)") (class "Default")
      (node (ref "U1") (pin "46") (pinfunction "PE15_46") (pintype "bidirectional"))
    )
  )
)
